# uC.net
KiCad netlist of a schematic drawn in Altium Designer
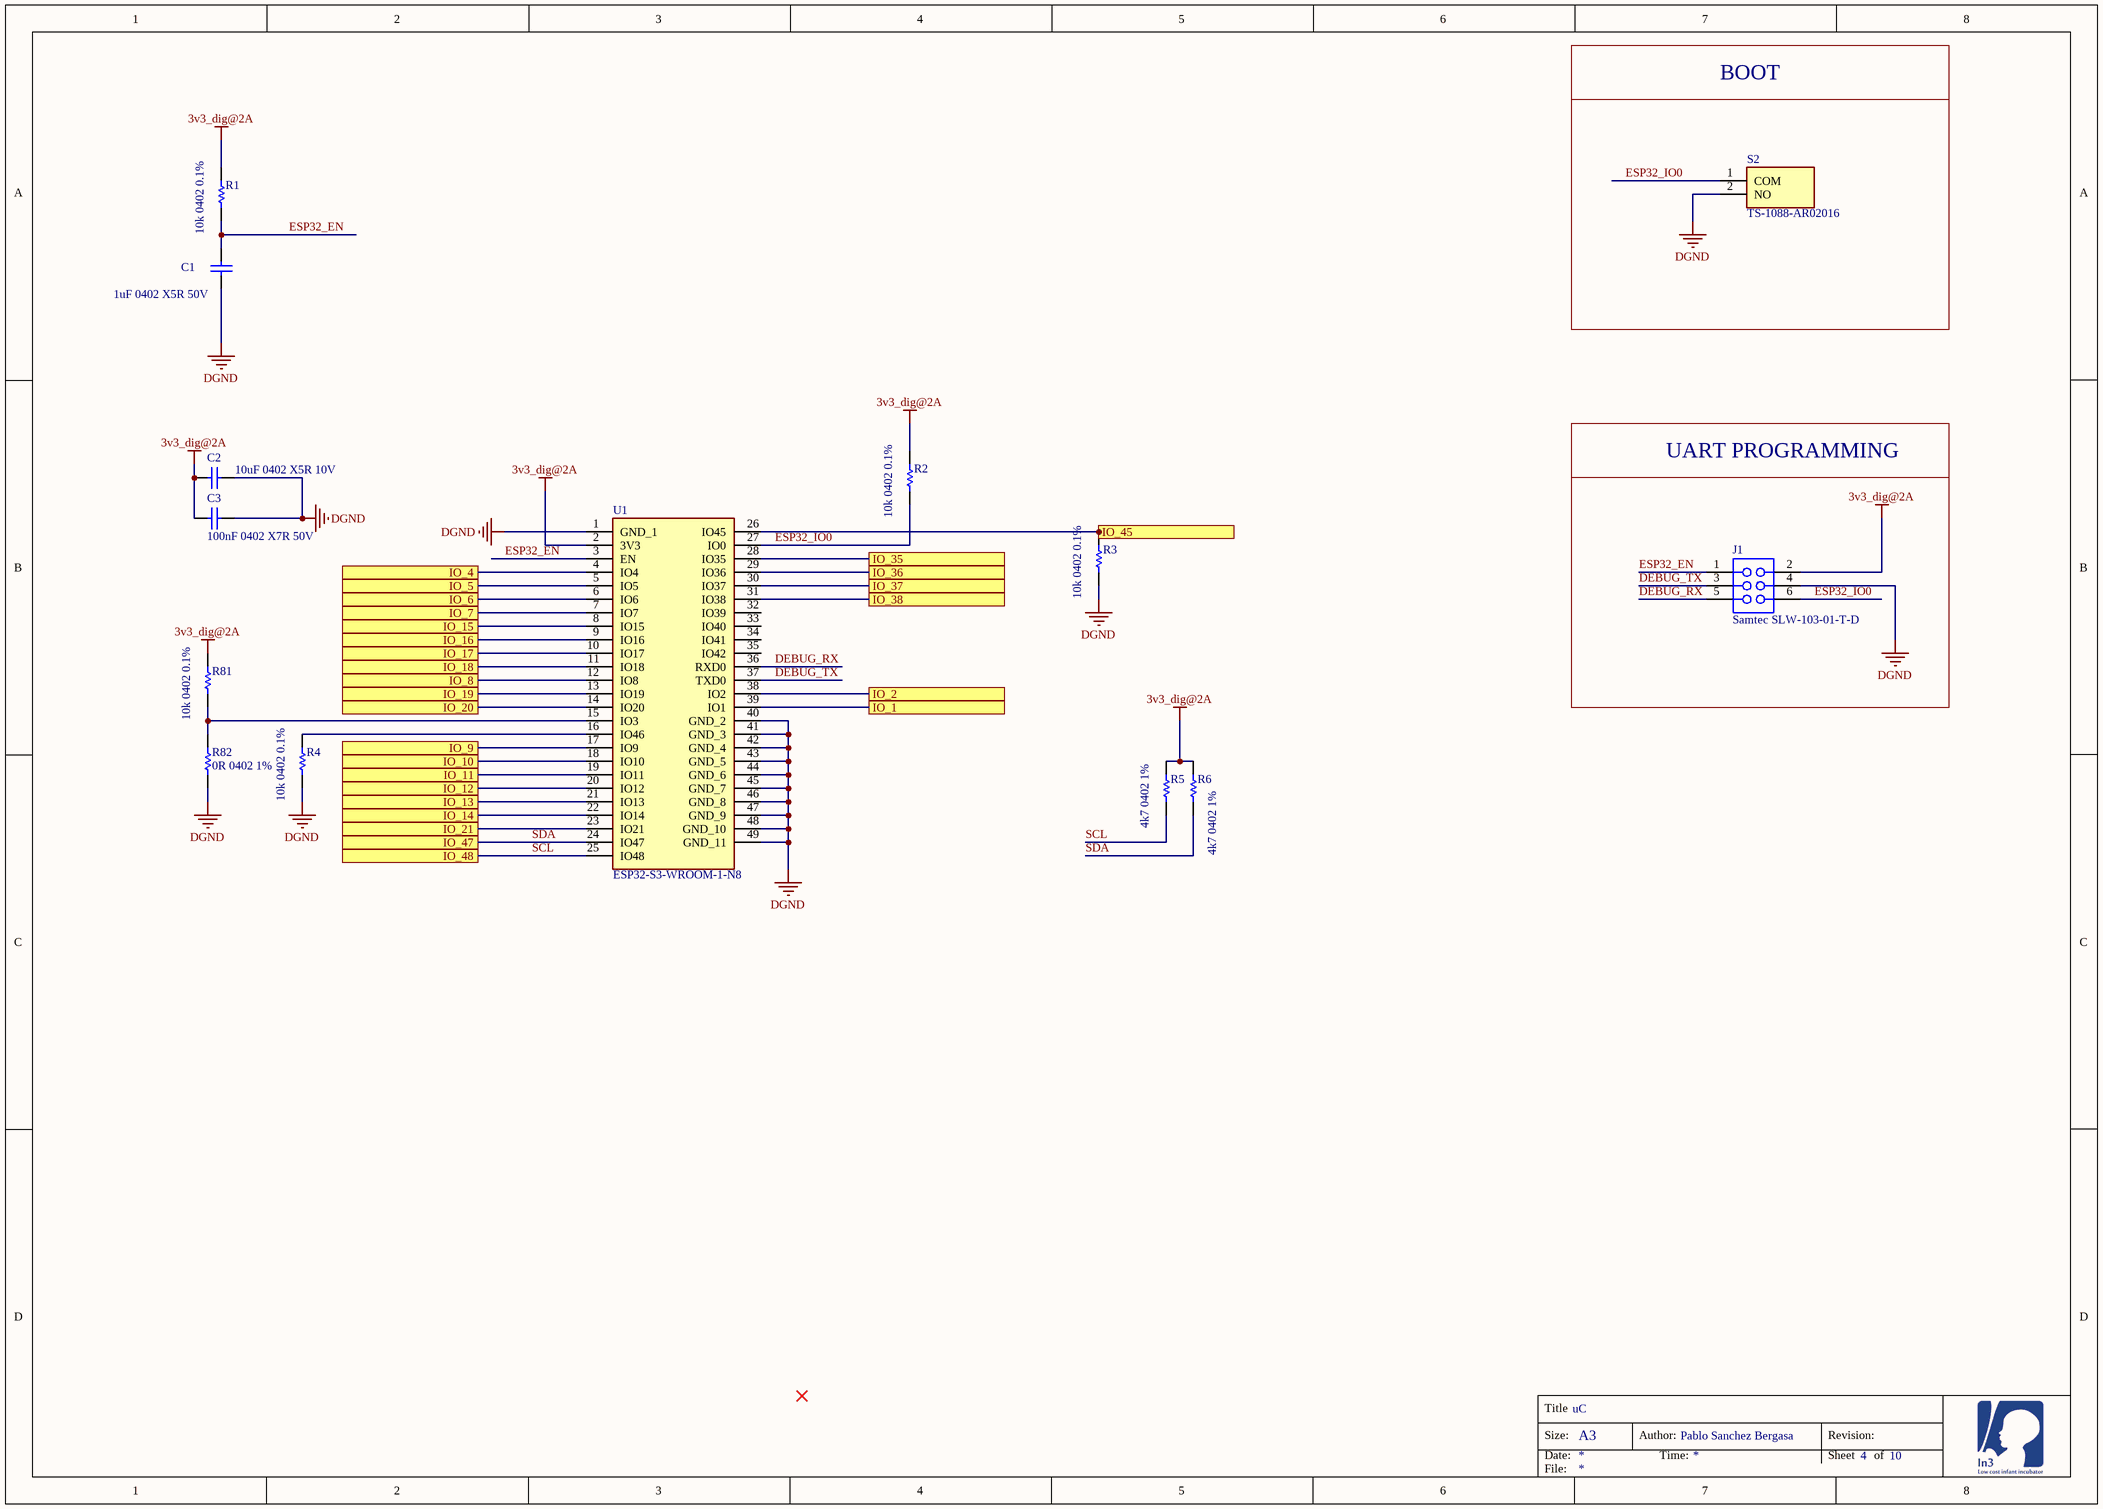
[diagram p0: uC.SchDoc]

(export (version "E")
  (design (tool "Eeschema 10.0.6"))
  (components
    (comp (ref "C1")
      (value "1uF 0402 X5R 50V")
      (footprint "CAPC1005X55X25NL5T10")
      (libsource (lib "Altium Content Vault") (part "CAP-NP-2"))
    )
    (comp (ref "C2")
      (value "10uF 0402 X5R 10V")
      (footprint "CAPC1005X55X25NL5T10")
      (libsource (lib "Altium Content Vault") (part "CAP-NP-2"))
    )
    (comp (ref "C3")
      (value "100nF 0402 X7R 50V")
      (footprint "CAPC1005X55X25NL5T10")
      (libsource (lib "Altium Content Vault") (part "CAP-NP-2"))
    )
    (comp (ref "J1")
      (value "Samtec SLW-103-01-T-D")
      (footprint "PCB-37z8hw1ej4f71bosen9e-1")
      (description "Dual Row Connector Female Samtec SLW-103-01-T-D")
      (fields (field (name "MANUFACTURER PART NUMBER") "SLW-103-01-T-D"))
      (libsource (lib "in3ator") (part "CMP-bcf575fbeff46332-1"))
    )
    (comp (ref "R1")
      (value "10k 0402 0.1%")
      (footprint "RESC1005X40X25ML05T10")
      (libsource (lib "Altium Content Vault") (part "RES"))
    )
    (comp (ref "R2")
      (value "10k 0402 0.1%")
      (footprint "RESC1005X40X25ML05T10")
      (libsource (lib "Altium Content Vault") (part "RES"))
    )
    (comp (ref "R3")
      (value "10k 0402 0.1%")
      (footprint "RESC1005X40X25ML05T10")
      (libsource (lib "Altium Content Vault") (part "RES"))
    )
    (comp (ref "R4")
      (value "10k 0402 0.1%")
      (footprint "RESC1005X40X25ML05T10")
      (libsource (lib "Altium Content Vault") (part "RES"))
    )
    (comp (ref "R5")
      (value "4k7 0402 1%")
      (footprint "RESC1005X40X25ML05T10")
      (libsource (lib "Altium Content Vault") (part "RES"))
    )
    (comp (ref "R6")
      (value "4k7 0402 1%")
      (footprint "RESC1005X40X25ML05T10")
      (libsource (lib "Altium Content Vault") (part "RES"))
    )
    (comp (ref "R81")
      (value "10k 0402 0.1%")
      (footprint "RESC1005X40X25ML05T10")
      (libsource (lib "Altium Content Vault") (part "RES"))
    )
    (comp (ref "R82")
      (value "0R 0402 1%")
      (footprint "RESC1005X40X25ML05T10")
      (libsource (lib "Altium Content Vault") (part "RES"))
    )
    (comp (ref "S2")
      (value "TS-1088-AR02016")
      (footprint "SamacSys:TS1088AR02016")
      (description "Switch")
      (libsource (lib "*") (part "TS-1088-AR02016"))
    )
    (comp (ref "U1")
      (value "ESP32-S3-WROOM-1-N8")
      (footprint "SamacSys:ESP32S3WROOM1N8R2")
      (description "Integrated Circuit")
      (fields (field (name "MOUSER PART NUMBER") "356-ESP32-S3WROOM1N8"))
      (libsource (lib "*") (part "ESP32-S3-WROOM-1-N8"))
    )
  )
  (nets
    (net (code "1") (name "/DEBUG_RX") (class "Default")
      (node (ref "J1") (pin "5") (pinfunction "5_5") (pintype "passive"))
      (node (ref "U1") (pin "36") (pinfunction "RXD0_36") (pintype "passive"))
    )
    (net (code "2") (name "/DEBUG_TX") (class "Default")
      (node (ref "J1") (pin "3") (pinfunction "3_3") (pintype "passive"))
      (node (ref "U1") (pin "37") (pinfunction "TXD0_37") (pintype "passive"))
    )
    (net (code "3") (name "/ESP32_EN") (class "Default")
      (node (ref "C1") (pin "2") (pinfunction "2_2") (pintype "passive"))
      (node (ref "J1") (pin "1") (pinfunction "1_1") (pintype "passive"))
      (node (ref "R1") (pin "1") (pinfunction "1_1") (pintype "passive"))
      (node (ref "U1") (pin "3") (pinfunction "EN_3") (pintype "passive"))
    )
    (net (code "4") (name "/ESP32_IO0") (class "Default")
      (node (ref "J1") (pin "6") (pinfunction "6_6") (pintype "passive"))
      (node (ref "R2") (pin "1") (pinfunction "1_1") (pintype "passive"))
      (node (ref "S2") (pin "1") (pinfunction "COM_1") (pintype "passive"))
      (node (ref "U1") (pin "27") (pinfunction "IO0_27") (pintype "passive"))
    )
    (net (code "5") (name "/IO_1") (class "Default")
      (node (ref "U1") (pin "39") (pinfunction "IO1_39") (pintype "passive"))
    )
    (net (code "6") (name "/IO_2") (class "Default")
      (node (ref "U1") (pin "38") (pinfunction "IO2_38") (pintype "passive"))
    )
    (net (code "7") (name "/IO_4") (class "Default")
      (node (ref "U1") (pin "4") (pinfunction "IO4_4") (pintype "passive"))
    )
    (net (code "8") (name "/IO_5") (class "Default")
      (node (ref "U1") (pin "5") (pinfunction "IO5_5") (pintype "passive"))
    )
    (net (code "9") (name "/IO_6") (class "Default")
      (node (ref "U1") (pin "6") (pinfunction "IO6_6") (pintype "passive"))
    )
    (net (code "10") (name "/IO_7") (class "Default")
      (node (ref "U1") (pin "7") (pinfunction "IO7_7") (pintype "passive"))
    )
    (net (code "11") (name "/IO_8") (class "Default")
      (node (ref "U1") (pin "12") (pinfunction "IO8_12") (pintype "passive"))
    )
    (net (code "12") (name "/IO_9") (class "Default")
      (node (ref "U1") (pin "17") (pinfunction "IO9_17") (pintype "passive"))
    )
    (net (code "13") (name "/IO_10") (class "Default")
      (node (ref "U1") (pin "18") (pinfunction "IO10_18") (pintype "passive"))
    )
    (net (code "14") (name "/IO_11") (class "Default")
      (node (ref "U1") (pin "19") (pinfunction "IO11_19") (pintype "passive"))
    )
    (net (code "15") (name "/IO_12") (class "Default")
      (node (ref "U1") (pin "20") (pinfunction "IO12_20") (pintype "passive"))
    )
    (net (code "16") (name "/IO_13") (class "Default")
      (node (ref "U1") (pin "21") (pinfunction "IO13_21") (pintype "passive"))
    )
    (net (code "17") (name "/IO_14") (class "Default")
      (node (ref "U1") (pin "22") (pinfunction "IO14_22") (pintype "passive"))
    )
    (net (code "18") (name "/IO_15") (class "Default")
      (node (ref "U1") (pin "8") (pinfunction "IO15_8") (pintype "passive"))
    )
    (net (code "19") (name "/IO_16") (class "Default")
      (node (ref "U1") (pin "9") (pinfunction "IO16_9") (pintype "passive"))
    )
    (net (code "20") (name "/IO_17") (class "Default")
      (node (ref "U1") (pin "10") (pinfunction "IO17_10") (pintype "passive"))
    )
    (net (code "21") (name "/IO_18") (class "Default")
      (node (ref "U1") (pin "11") (pinfunction "IO18_11") (pintype "passive"))
    )
    (net (code "22") (name "/IO_19") (class "Default")
      (node (ref "U1") (pin "13") (pinfunction "IO19_13") (pintype "passive"))
    )
    (net (code "23") (name "/IO_20") (class "Default")
      (node (ref "U1") (pin "14") (pinfunction "IO20_14") (pintype "passive"))
    )
    (net (code "24") (name "/IO_21") (class "Default")
      (node (ref "U1") (pin "23") (pinfunction "IO21_23") (pintype "passive"))
    )
    (net (code "25") (name "/IO_35") (class "Default")
      (node (ref "U1") (pin "28") (pinfunction "IO35_28") (pintype "passive"))
    )
    (net (code "26") (name "/IO_36") (class "Default")
      (node (ref "U1") (pin "29") (pinfunction "IO36_29") (pintype "passive"))
    )
    (net (code "27") (name "/IO_37") (class "Default")
      (node (ref "U1") (pin "30") (pinfunction "IO37_30") (pintype "passive"))
    )
    (net (code "28") (name "/IO_38") (class "Default")
      (node (ref "U1") (pin "31") (pinfunction "IO38_31") (pintype "passive"))
    )
    (net (code "29") (name "/IO_45") (class "Default")
      (node (ref "R3") (pin "2") (pinfunction "2_2") (pintype "passive"))
      (node (ref "U1") (pin "26") (pinfunction "IO45_26") (pintype "passive"))
    )
    (net (code "30") (name "/SCL") (class "Default")
      (node (ref "R5") (pin "2") (pinfunction "2_2") (pintype "passive"))
      (node (ref "U1") (pin "25") (pinfunction "IO48_25") (pintype "passive"))
    )
    (net (code "31") (name "/SDA") (class "Default")
      (node (ref "R6") (pin "2") (pinfunction "2_2") (pintype "passive"))
      (node (ref "U1") (pin "24") (pinfunction "IO47_24") (pintype "passive"))
    )
    (net (code "32") (name "3v3_dig@2A") (class "Default")
      (node (ref "C2") (pin "2") (pinfunction "2_2") (pintype "passive"))
      (node (ref "C3") (pin "2") (pinfunction "2_2") (pintype "passive"))
      (node (ref "J1") (pin "2") (pinfunction "2_2") (pintype "passive"))
      (node (ref "R1") (pin "2") (pinfunction "2_2") (pintype "passive"))
      (node (ref "R2") (pin "2") (pinfunction "2_2") (pintype "passive"))
      (node (ref "R5") (pin "1") (pinfunction "1_1") (pintype "passive"))
      (node (ref "R6") (pin "1") (pinfunction "1_1") (pintype "passive"))
      (node (ref "R81") (pin "2") (pinfunction "2_2") (pintype "passive"))
      (node (ref "U1") (pin "2") (pinfunction "3V3_2") (pintype "passive"))
    )
    (net (code "33") (name "DGND") (class "Default")
      (node (ref "C1") (pin "1") (pinfunction "1_1") (pintype "passive"))
      (node (ref "C2") (pin "1") (pinfunction "1_1") (pintype "passive"))
      (node (ref "C3") (pin "1") (pinfunction "1_1") (pintype "passive"))
      (node (ref "J1") (pin "4") (pinfunction "4_4") (pintype "passive"))
      (node (ref "R3") (pin "1") (pinfunction "1_1") (pintype "passive"))
      (node (ref "R4") (pin "1") (pinfunction "1_1") (pintype "passive"))
      (node (ref "R82") (pin "2") (pinfunction "2_2") (pintype "passive"))
      (node (ref "S2") (pin "2") (pinfunction "NO_2") (pintype "passive"))
      (node (ref "U1") (pin "1") (pinfunction "GND_1_1") (pintype "passive"))
      (node (ref "U1") (pin "40") (pinfunction "GND_2_40") (pintype "passive"))
      (node (ref "U1") (pin "41") (pinfunction "GND_3_41") (pintype "passive"))
      (node (ref "U1") (pin "42") (pinfunction "GND_4_42") (pintype "passive"))
      (node (ref "U1") (pin "43") (pinfunction "GND_5_43") (pintype "passive"))
      (node (ref "U1") (pin "44") (pinfunction "GND_6_44") (pintype "passive"))
      (node (ref "U1") (pin "45") (pinfunction "GND_7_45") (pintype "passive"))
      (node (ref "U1") (pin "46") (pinfunction "GND_8_46") (pintype "passive"))
      (node (ref "U1") (pin "47") (pinfunction "GND_9_47") (pintype "passive"))
      (node (ref "U1") (pin "48") (pinfunction "GND_10_48") (pintype "passive"))
      (node (ref "U1") (pin "49") (pinfunction "GND_11_49") (pintype "passive"))
    )
    (net (code "34") (name "Net-(U1-IO3)") (class "Default")
      (node (ref "R81") (pin "1") (pinfunction "1_1") (pintype "passive"))
      (node (ref "R82") (pin "1") (pinfunction "1_1") (pintype "passive"))
      (node (ref "U1") (pin "15") (pinfunction "IO3_15") (pintype "passive"))
    )
    (net (code "35") (name "Net-(U1-IO46)") (class "Default")
      (node (ref "R4") (pin "2") (pinfunction "2_2") (pintype "passive"))
      (node (ref "U1") (pin "16") (pinfunction "IO46_16") (pintype "passive"))
    )
    (net (code "36") (name "unconnected-(U1-IO39-Pad32)") (class "Default")
      (node (ref "U1") (pin "32") (pinfunction "IO39_32") (pintype "passive"))
    )
    (net (code "37") (name "unconnected-(U1-IO40-Pad33)") (class "Default")
      (node (ref "U1") (pin "33") (pinfunction "IO40_33") (pintype "passive"))
    )
    (net (code "38") (name "unconnected-(U1-IO41-Pad34)") (class "Default")
      (node (ref "U1") (pin "34") (pinfunction "IO41_34") (pintype "passive"))
    )
    (net (code "39") (name "unconnected-(U1-IO42-Pad35)") (class "Default")
      (node (ref "U1") (pin "35") (pinfunction "IO42_35") (pintype "passive"))
    )
  )
)
